# Fri3D_Air_2018_01.net
KiCad netlist of a schematic drawn in Altium Designer
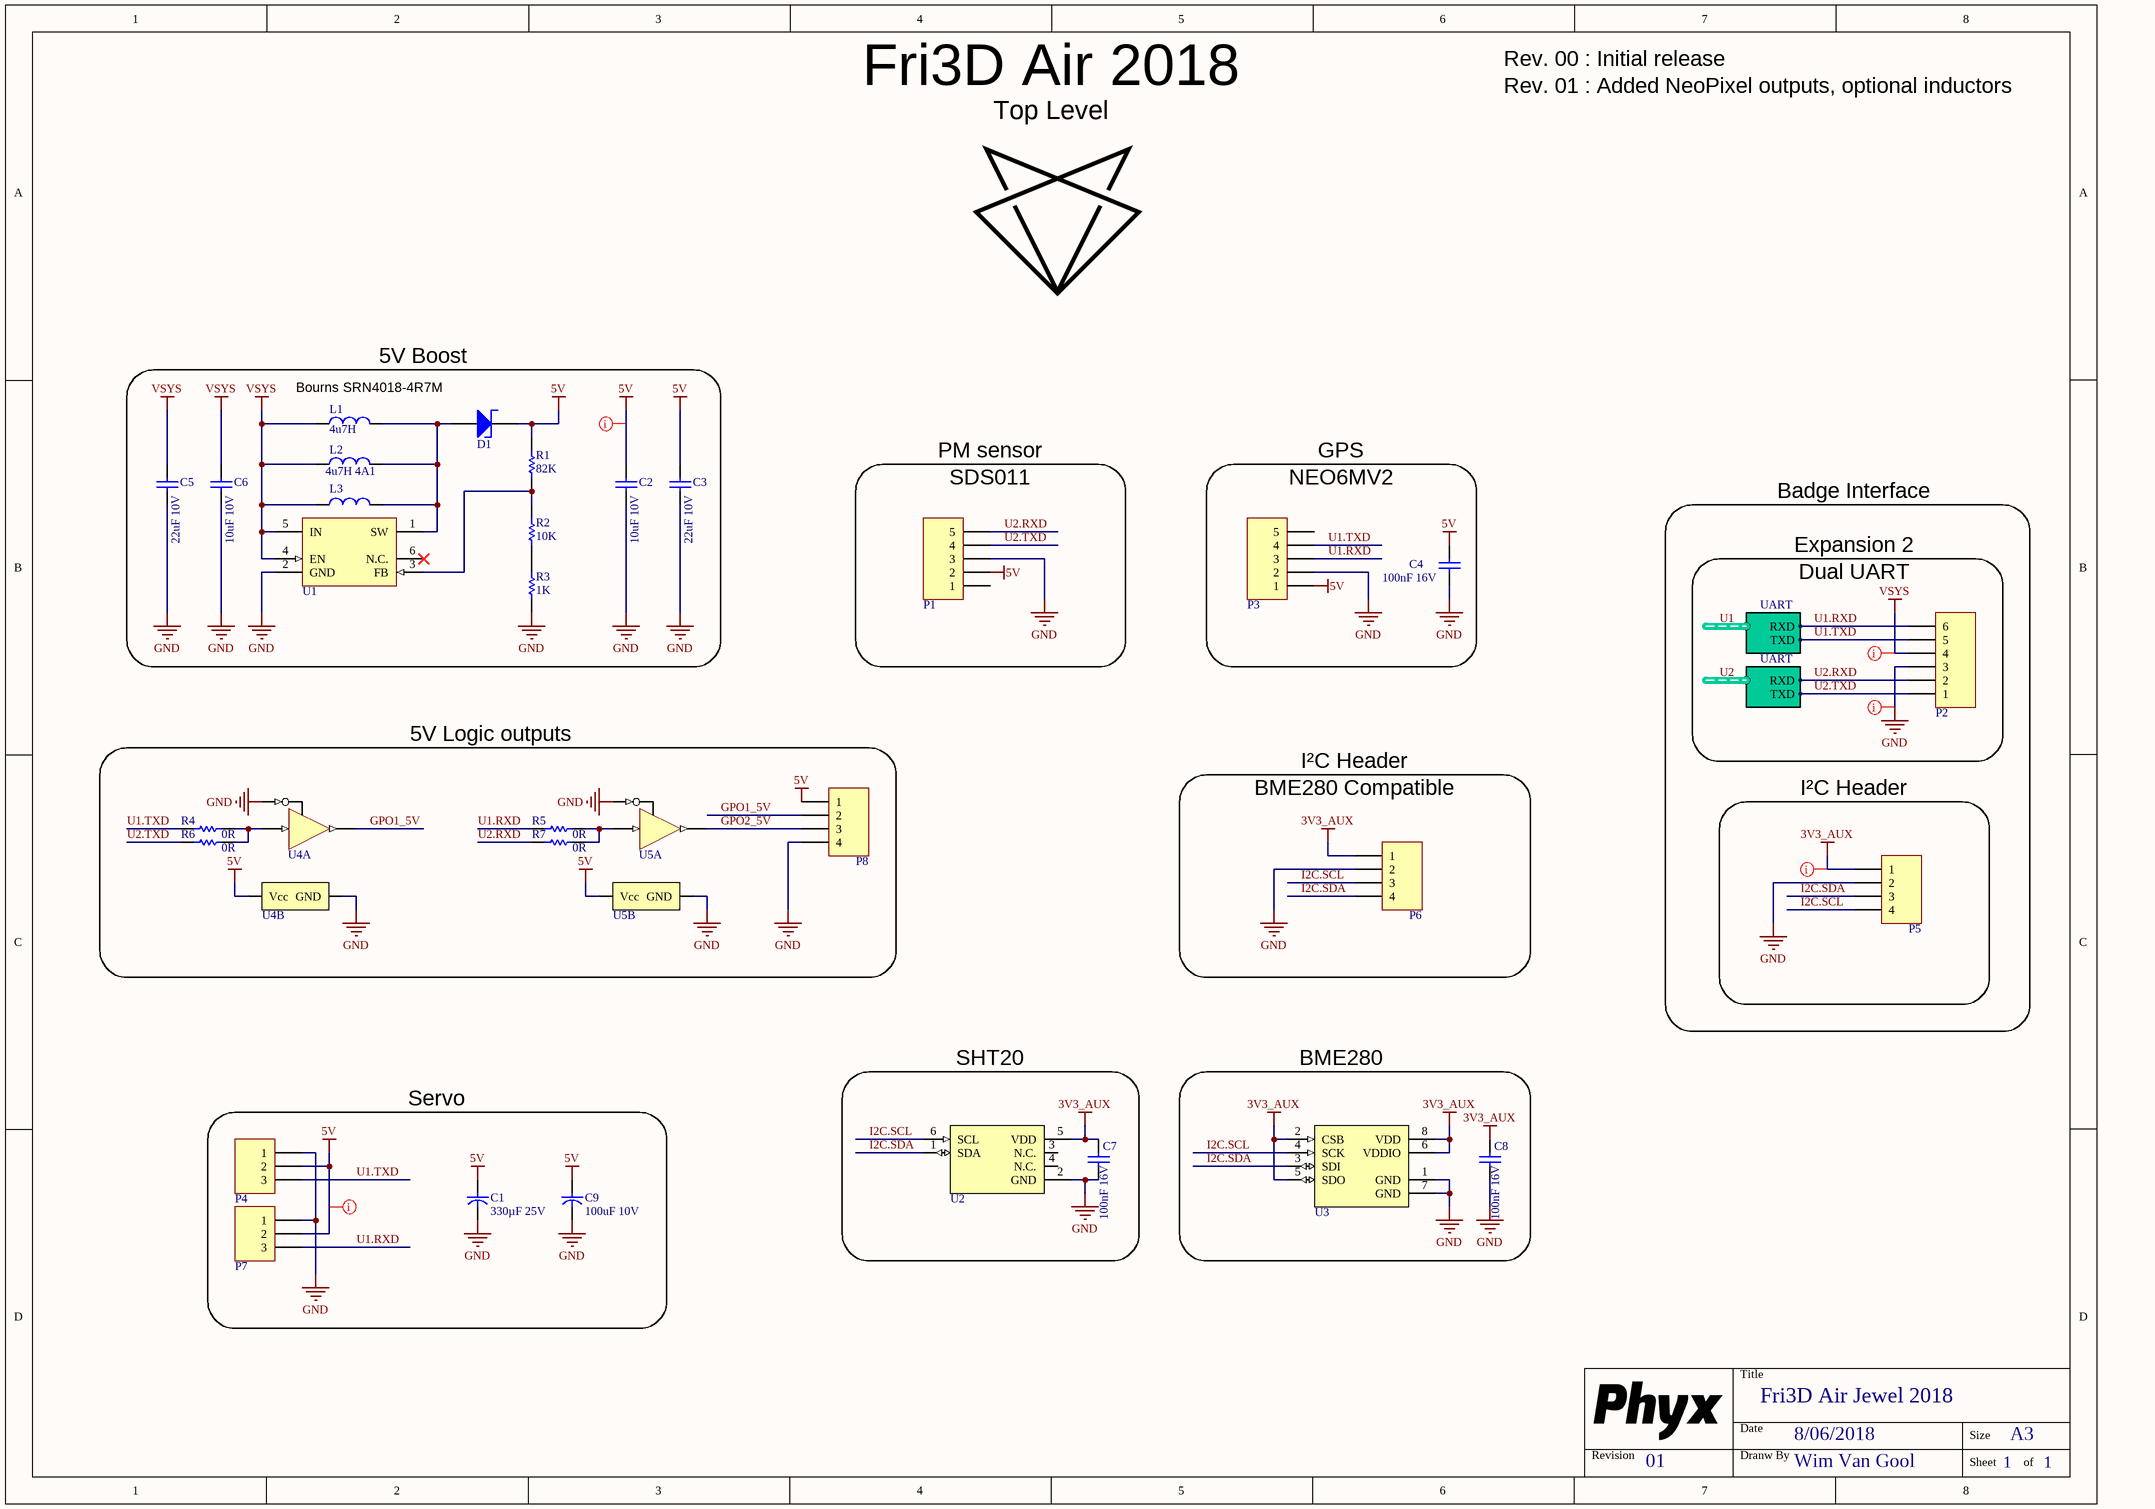
[diagram p0: Fri3D_Air_2018_01.SchDoc]

(export (version "E")
  (design (tool "Eeschema 10.0.6"))
  (components
    (comp (ref "C1")
      (value "330µF 25V")
      (footprint "C_8x15_3.5mm")
      (description "Capacitor electrolyt")
      (fields (field (name "Comment") "CAP_POL"))
      (libsource (lib "Phyx_Components") (part "CAP_POL"))
    )
    (comp (ref "C2")
      (value "10uF 10V")
      (footprint "C0805_N")
      (description "Capacitor Ceramic")
      (fields (field (name "Comment") "CAP_CERAMIC"))
      (libsource (lib "Phyx_Components") (part "CAP_CERAMIC"))
    )
    (comp (ref "C3")
      (value "22uF 10V")
      (footprint "C1210_N")
      (description "Capacitor Ceramic")
      (fields (field (name "Comment") "CAP_CERAMIC"))
      (libsource (lib "Phyx_Components") (part "CAP_CERAMIC"))
    )
    (comp (ref "C4")
      (value "100nF 16V")
      (footprint "C0603_N")
      (description "Capacitor Ceramic")
      (libsource (lib "Phyx_Components") (part "CAP_CERAMIC"))
    )
    (comp (ref "C5")
      (value "22uF 10V")
      (footprint "C1210_N")
      (description "Capacitor Ceramic")
      (fields (field (name "Comment") "CAP_CERAMIC"))
      (libsource (lib "Phyx_Components") (part "CAP_CERAMIC"))
    )
    (comp (ref "C6")
      (value "10uF 10V")
      (footprint "C0805_N")
      (description "Capacitor Ceramic")
      (fields (field (name "Comment") "CAP_CERAMIC"))
      (libsource (lib "Phyx_Components") (part "CAP_CERAMIC"))
    )
    (comp (ref "C7")
      (value "100nF 16V")
      (footprint "C0603_N")
      (description "Capacitor Ceramic")
      (libsource (lib "Phyx_Components") (part "CAP_CERAMIC"))
    )
    (comp (ref "C8")
      (value "100nF 16V")
      (footprint "C0603_N")
      (description "Capacitor Ceramic")
      (libsource (lib "Phyx_Components") (part "CAP_CERAMIC"))
    )
    (comp (ref "C9")
      (value "100uF 10V")
      (footprint "C_5x11_2mm")
      (description "Capacitor electrolyt")
      (fields (field (name "Comment") "CAP_POL"))
      (libsource (lib "Phyx_Components") (part "CAP_POL"))
    )
    (comp (ref "D1")
      (value "TSS83L45 MWG Schottky ULTRAFAST, 3A, 45V")
      (footprint "TS_SOD128")
      (description "=Description")
      (libsource (lib "Phyx_Components") (part "Schottky_21"))
    )
    (comp (ref "L1")
      (value "4u7H")
      (footprint "SNL_SWPA4020")
      (fields (field (name "Comment") "SWPA4020S4R7MT"))
      (libsource (lib "Phyx_Components") (part "INDUCTOR"))
    )
    (comp (ref "L2")
      (value "4u7H 4A1")
      (footprint "TAI_NRS8040")
      (fields (field (name "Comment") "NRS8040T4R7NJGJ"))
      (libsource (lib "Phyx_Components") (part "INDUCTOR"))
    )
    (comp (ref "L3")
      (value "VLC6045T-3R3N")
      (footprint "IND_6045")
      (libsource (lib "Phyx_Components") (part "INDUCTOR"))
    )
    (comp (ref "P1")
      (value "Header 2.5mm RA Shrouded 5")
      (footprint "WE_68800511722")
      (libsource (lib "Phyx_Components") (part "Header 5"))
    )
    (comp (ref "P2")
      (value "Header 6")
      (footprint "HDR1X6")
      (libsource (lib "Phyx_Components") (part "Header 6"))
    )
    (comp (ref "P3")
      (value "Header 5")
      (footprint "HDR1X5")
      (libsource (lib "Phyx_Components") (part "Header 5"))
    )
    (comp (ref "P4")
      (value "Header 3")
      (footprint "HDR1X3")
      (libsource (lib "Phyx_Components") (part "Header 3"))
    )
    (comp (ref "P5")
      (value "Header 4")
      (footprint "HDR1X4")
      (libsource (lib "Phyx_Components") (part "Header 4"))
    )
    (comp (ref "P6")
      (value "Header 4")
      (footprint "HDR1X4")
      (libsource (lib "Phyx_Components") (part "Header 4"))
    )
    (comp (ref "P7")
      (value "Header 3")
      (footprint "HDR1X3")
      (libsource (lib "Phyx_Components") (part "Header 3"))
    )
    (comp (ref "P8")
      (value "Header 4")
      (footprint "HDR1X4")
      (libsource (lib "Phyx_Components") (part "Header 4"))
    )
    (comp (ref "R1")
      (value "82K")
      (footprint "R0603_N")
      (fields (field (name "Comment") "RESISTOR"))
      (libsource (lib "Phyx_Components") (part "RESISTOR"))
    )
    (comp (ref "R2")
      (value "10K")
      (footprint "R0603_N")
      (fields (field (name "Comment") "RESISTOR"))
      (libsource (lib "Phyx_Components") (part "RESISTOR"))
    )
    (comp (ref "R3")
      (value "1K")
      (footprint "R0603_N")
      (fields (field (name "Comment") "RESISTOR"))
      (libsource (lib "Phyx_Components") (part "RESISTOR"))
    )
    (comp (ref "R4")
      (value "0R")
      (footprint "R0603_N")
      (fields (field (name "Comment") "RESISTOR"))
      (libsource (lib "Phyx_Components") (part "RESISTOR"))
    )
    (comp (ref "R5")
      (value "0R")
      (footprint "R0603_N")
      (fields (field (name "Comment") "RESISTOR"))
      (libsource (lib "Phyx_Components") (part "RESISTOR"))
    )
    (comp (ref "R6")
      (value "0R")
      (footprint "R0603_N")
      (fields (field (name "Comment") "RESISTOR"))
      (libsource (lib "Phyx_Components") (part "RESISTOR"))
    )
    (comp (ref "R7")
      (value "0R")
      (footprint "R0603_N")
      (fields (field (name "Comment") "RESISTOR"))
      (libsource (lib "Phyx_Components") (part "RESISTOR"))
    )
    (comp (ref "U1")
      (value "High Efficiency 1.2MHz 2A Step Up Converter  SX1308")
      (footprint "SOT23-6")
      (description "=Description")
      (libsource (lib "Phyx_Components") (part "SX1308_Boost"))
    )
    (comp (ref "U2")
      (value "Sensirion SHT20 temperature and humidity sensor I2C")
      (footprint "SNS_DFN6")
      (description "=Description")
      (libsource (lib "Phyx_Components") (part "SHT2x"))
    )
    (comp (ref "U3")
      (value "Bosch BME280 Temperature, humidity, pressure sensor I2C")
      (footprint "BOS_BME280")
      (description "=Description")
      (libsource (lib "Phyx_Components") (part "BOS_BME280"))
    )
    (comp (ref "U4")
      (value "SN74AHCT1G125DCKR  Buffer, Tri-State, 4.5V to 5.5V")
      (footprint "TI_DBV_R-PDSO-G5")
      (description "=Description")
      (libsource (lib "Phyx_Components") (part "SN74AHCT1G125"))
    )
    (comp (ref "U5")
      (value "SN74AHCT1G125DCKR  Buffer, Tri-State, 4.5V to 5.5V")
      (footprint "TI_DBV_R-PDSO-G5")
      (description "=Description")
      (libsource (lib "Phyx_Components") (part "SN74AHCT1G125"))
    )
  )
  (nets
    (net (code "3") (name "/GPO1_5V") (class "Default")
      (node (ref "P8") (pin "2") (pinfunction "2_2") (pintype "passive"))
      (node (ref "U4") (pin "4") (pinfunction "Y_4") (pintype "output"))
    )
    (net (code "4") (name "/GPO2_5V") (class "Default")
      (node (ref "P8") (pin "3") (pinfunction "3_3") (pintype "passive"))
      (node (ref "U5") (pin "4") (pinfunction "Y_4") (pintype "output"))
    )
    (net (code "5") (name "/I2C.SCL") (class "Default")
      (node (ref "P5") (pin "4") (pinfunction "4_4") (pintype "passive"))
      (node (ref "P6") (pin "3") (pinfunction "3_3") (pintype "passive"))
      (node (ref "U2") (pin "6") (pinfunction "SCL_6") (pintype "input"))
      (node (ref "U3") (pin "4") (pinfunction "SCK_4") (pintype "input"))
    )
    (net (code "6") (name "/I2C.SDA") (class "Default")
      (node (ref "P5") (pin "3") (pinfunction "3_3") (pintype "passive"))
      (node (ref "P6") (pin "4") (pinfunction "4_4") (pintype "passive"))
      (node (ref "U2") (pin "1") (pinfunction "SDA_1") (pintype "bidirectional"))
      (node (ref "U3") (pin "3") (pinfunction "SDI_3") (pintype "bidirectional"))
    )
    (net (code "7") (name "/U1.RXD") (class "Default")
      (node (ref "P2") (pin "6") (pinfunction "6_6") (pintype "passive"))
      (node (ref "P3") (pin "3") (pinfunction "3_3") (pintype "passive"))
      (node (ref "P7") (pin "3") (pinfunction "3_3") (pintype "passive"))
      (node (ref "R5") (pin "2") (pinfunction "2_2") (pintype "passive"))
    )
    (net (code "8") (name "/U1.TXD") (class "Default")
      (node (ref "P2") (pin "5") (pinfunction "5_5") (pintype "passive"))
      (node (ref "P3") (pin "4") (pinfunction "4_4") (pintype "passive"))
      (node (ref "P4") (pin "3") (pinfunction "3_3") (pintype "passive"))
      (node (ref "R4") (pin "2") (pinfunction "2_2") (pintype "passive"))
    )
    (net (code "10") (name "/U2.RXD") (class "Default")
      (node (ref "P1") (pin "5") (pinfunction "5_5") (pintype "passive"))
      (node (ref "P2") (pin "2") (pinfunction "2_2") (pintype "passive"))
      (node (ref "R7") (pin "2") (pinfunction "2_2") (pintype "passive"))
    )
    (net (code "11") (name "/U2.TXD") (class "Default")
      (node (ref "P1") (pin "4") (pinfunction "4_4") (pintype "passive"))
      (node (ref "P2") (pin "1") (pinfunction "1_1") (pintype "passive"))
      (node (ref "R6") (pin "2") (pinfunction "2_2") (pintype "passive"))
    )
    (net (code "13") (name "3V3_AUX") (class "Default")
      (node (ref "C7") (pin "1") (pinfunction "1_1") (pintype "passive"))
      (node (ref "C8") (pin "1") (pinfunction "1_1") (pintype "passive"))
      (node (ref "P5") (pin "1") (pinfunction "1_1") (pintype "passive"))
      (node (ref "P6") (pin "1") (pinfunction "1_1") (pintype "passive"))
      (node (ref "U2") (pin "5") (pinfunction "VDD_5") (pintype "power_in"))
      (node (ref "U3") (pin "2") (pinfunction "CSB_2") (pintype "input"))
      (node (ref "U3") (pin "5") (pinfunction "SDO_5") (pintype "bidirectional"))
      (node (ref "U3") (pin "6") (pinfunction "VDDIO_6") (pintype "power_in"))
      (node (ref "U3") (pin "8") (pinfunction "VDD_8") (pintype "power_in"))
    )
    (net (code "14") (name "5V") (class "Default")
      (node (ref "C1") (pin "1") (pinfunction "1_1") (pintype "passive"))
      (node (ref "C2") (pin "1") (pinfunction "1_1") (pintype "passive"))
      (node (ref "C3") (pin "1") (pinfunction "1_1") (pintype "passive"))
      (node (ref "C4") (pin "1") (pinfunction "1_1") (pintype "passive"))
      (node (ref "C9") (pin "1") (pinfunction "1_1") (pintype "passive"))
      (node (ref "D1") (pin "1") (pinfunction "C_1") (pintype "passive"))
      (node (ref "P1") (pin "2") (pinfunction "2_2") (pintype "passive"))
      (node (ref "P3") (pin "1") (pinfunction "1_1") (pintype "passive"))
      (node (ref "P4") (pin "2") (pinfunction "2_2") (pintype "passive"))
      (node (ref "P7") (pin "2") (pinfunction "2_2") (pintype "passive"))
      (node (ref "P8") (pin "1") (pinfunction "1_1") (pintype "passive"))
      (node (ref "R1") (pin "1") (pinfunction "1_1") (pintype "passive"))
      (node (ref "U4") (pin "5") (pinfunction "Vcc_5") (pintype "power_in"))
      (node (ref "U5") (pin "5") (pinfunction "Vcc_5") (pintype "power_in"))
    )
    (net (code "15") (name "GND") (class "Default")
      (node (ref "C1") (pin "2") (pinfunction "2_2") (pintype "passive"))
      (node (ref "C2") (pin "2") (pinfunction "2_2") (pintype "passive"))
      (node (ref "C3") (pin "2") (pinfunction "2_2") (pintype "passive"))
      (node (ref "C4") (pin "2") (pinfunction "2_2") (pintype "passive"))
      (node (ref "C5") (pin "2") (pinfunction "2_2") (pintype "passive"))
      (node (ref "C6") (pin "2") (pinfunction "2_2") (pintype "passive"))
      (node (ref "C7") (pin "2") (pinfunction "2_2") (pintype "passive"))
      (node (ref "C8") (pin "2") (pinfunction "2_2") (pintype "passive"))
      (node (ref "C9") (pin "2") (pinfunction "2_2") (pintype "passive"))
      (node (ref "P1") (pin "3") (pinfunction "3_3") (pintype "passive"))
      (node (ref "P2") (pin "3") (pinfunction "3_3") (pintype "passive"))
      (node (ref "P3") (pin "2") (pinfunction "2_2") (pintype "passive"))
      (node (ref "P4") (pin "1") (pinfunction "1_1") (pintype "passive"))
      (node (ref "P5") (pin "2") (pinfunction "2_2") (pintype "passive"))
      (node (ref "P6") (pin "2") (pinfunction "2_2") (pintype "passive"))
      (node (ref "P7") (pin "1") (pinfunction "1_1") (pintype "passive"))
      (node (ref "P8") (pin "4") (pinfunction "4_4") (pintype "passive"))
      (node (ref "R3") (pin "2") (pinfunction "2_2") (pintype "passive"))
      (node (ref "U1") (pin "2") (pinfunction "GND_2") (pintype "power_in"))
      (node (ref "U2") (pin "2") (pinfunction "GND_2") (pintype "power_in"))
      (node (ref "U3") (pin "1") (pinfunction "GND_1") (pintype "power_in"))
      (node (ref "U3") (pin "7") (pinfunction "GND_7") (pintype "power_in"))
      (node (ref "U4") (pin "1") (pinfunction "~{OE}_1") (pintype "input"))
      (node (ref "U4") (pin "3") (pinfunction "GND_3") (pintype "power_in"))
      (node (ref "U5") (pin "1") (pinfunction "~{OE}_1") (pintype "input"))
      (node (ref "U5") (pin "3") (pinfunction "GND_3") (pintype "power_in"))
    )
    (net (code "16") (name "Net-(D1-A)") (class "Default")
      (node (ref "D1") (pin "2") (pinfunction "A_2") (pintype "passive"))
      (node (ref "L1") (pin "2") (pinfunction "2_2") (pintype "passive"))
      (node (ref "L2") (pin "2") (pinfunction "2_2") (pintype "passive"))
      (node (ref "L3") (pin "2") (pinfunction "2_2") (pintype "passive"))
      (node (ref "U1") (pin "1") (pinfunction "SW_1") (pintype "power_in"))
    )
    (net (code "17") (name "Net-(R2-Pad2)") (class "Default")
      (node (ref "R2") (pin "2") (pinfunction "2_2") (pintype "passive"))
      (node (ref "R3") (pin "1") (pinfunction "1_1") (pintype "passive"))
    )
    (net (code "18") (name "Net-(U1-FB)") (class "Default")
      (node (ref "R1") (pin "2") (pinfunction "2_2") (pintype "passive"))
      (node (ref "R2") (pin "1") (pinfunction "1_1") (pintype "passive"))
      (node (ref "U1") (pin "3") (pinfunction "FB_3") (pintype "input"))
    )
    (net (code "19") (name "Net-(U4A-A)") (class "Default")
      (node (ref "R4") (pin "1") (pinfunction "1_1") (pintype "passive"))
      (node (ref "R6") (pin "1") (pinfunction "1_1") (pintype "passive"))
      (node (ref "U4") (pin "2") (pinfunction "A_2") (pintype "input"))
    )
    (net (code "20") (name "Net-(U5A-A)") (class "Default")
      (node (ref "R5") (pin "1") (pinfunction "1_1") (pintype "passive"))
      (node (ref "R7") (pin "1") (pinfunction "1_1") (pintype "passive"))
      (node (ref "U5") (pin "2") (pinfunction "A_2") (pintype "input"))
    )
    (net (code "21") (name "VSYS") (class "Default")
      (node (ref "C5") (pin "1") (pinfunction "1_1") (pintype "passive"))
      (node (ref "C6") (pin "1") (pinfunction "1_1") (pintype "passive"))
      (node (ref "L1") (pin "1") (pinfunction "1_1") (pintype "passive"))
      (node (ref "L2") (pin "1") (pinfunction "1_1") (pintype "passive"))
      (node (ref "L3") (pin "1") (pinfunction "1_1") (pintype "passive"))
      (node (ref "P2") (pin "4") (pinfunction "4_4") (pintype "passive"))
      (node (ref "U1") (pin "4") (pinfunction "EN_4") (pintype "input"))
      (node (ref "U1") (pin "5") (pinfunction "IN_5") (pintype "power_in"))
    )
    (net (code "22") (name "unconnected-(P1-Pad1)") (class "Default")
      (node (ref "P1") (pin "1") (pinfunction "1_1") (pintype "passive"))
    )
    (net (code "23") (name "unconnected-(P3-Pad5)") (class "Default")
      (node (ref "P3") (pin "5") (pinfunction "5_5") (pintype "passive"))
    )
    (net (code "24") (name "unconnected-(U1-N.C.-Pad6)") (class "Default")
      (node (ref "U1") (pin "6") (pinfunction "N.C._6") (pintype "power_in+no_connect"))
    )
    (net (code "25") (name "unconnected-(U2-N.C.-Pad3)") (class "Default")
      (node (ref "U2") (pin "3") (pinfunction "N.C._3") (pintype "passive"))
    )
    (net (code "26") (name "unconnected-(U2-N.C.-Pad4)") (class "Default")
      (node (ref "U2") (pin "4") (pinfunction "N.C._4") (pintype "passive"))
    )
  )
)
